# schemat.net
KiCad netlist of a schematic drawn in EAGLE
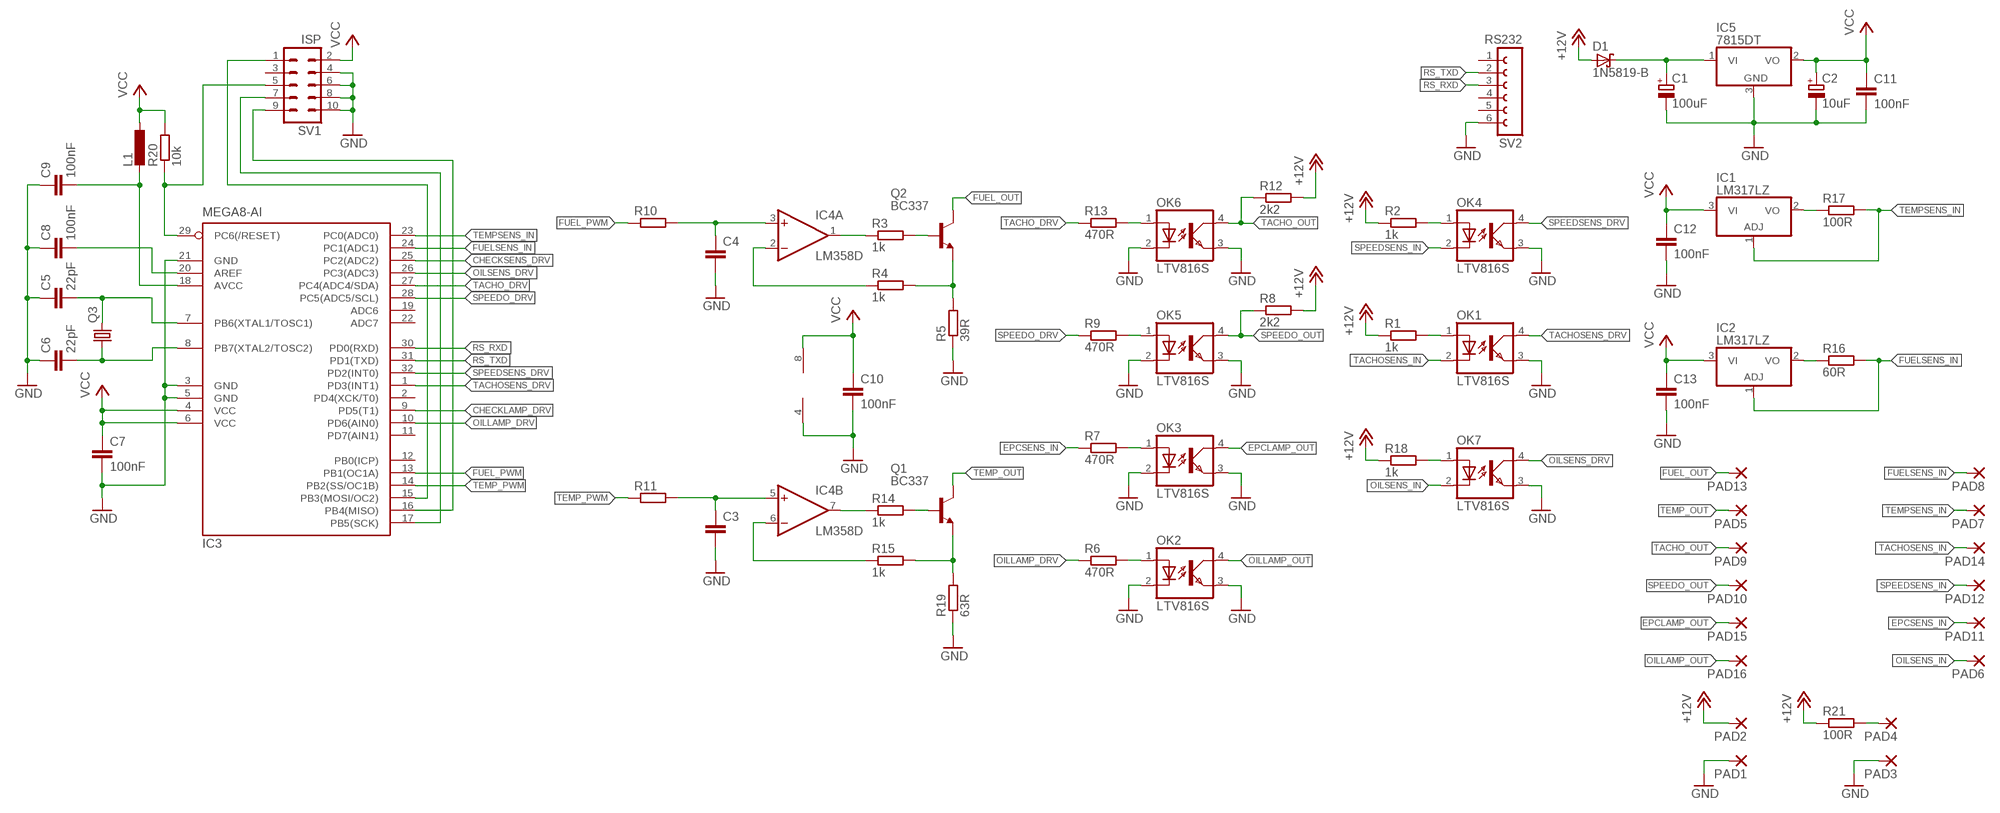
[diagram p0: schematic, sheet 1]

(export (version "E")
  (design (tool "Eeschema 10.0.6"))
  (components
    (comp (ref "C1")
      (value "100uF")
      (footprint "eagle-import:E2,5-6")
      (libsource (lib "eagle-import") (part "CPOL-EUE2.5-6"))
    )
    (comp (ref "C2")
      (value "10uF")
      (footprint "eagle-import:E2,5-6")
      (libsource (lib "eagle-import") (part "CPOL-EUE2.5-6"))
    )
    (comp (ref "C3")
      (value "C-EU025-025X050")
      (footprint "eagle-import:C025-025X050")
      (libsource (lib "eagle-import") (part "C-EU025-025X050"))
    )
    (comp (ref "C4")
      (value "C-EU025-025X050")
      (footprint "eagle-import:C025-025X050")
      (libsource (lib "eagle-import") (part "C-EU025-025X050"))
    )
    (comp (ref "C5")
      (value "22pF")
      (footprint "eagle-import:C0805")
      (libsource (lib "eagle-import") (part "C-EUC0805"))
    )
    (comp (ref "C6")
      (value "22pF")
      (footprint "eagle-import:C0805")
      (libsource (lib "eagle-import") (part "C-EUC0805"))
    )
    (comp (ref "C7")
      (value "100nF")
      (footprint "eagle-import:C0805")
      (libsource (lib "eagle-import") (part "C-EUC0805"))
    )
    (comp (ref "C8")
      (value "100nF")
      (footprint "eagle-import:C0805")
      (libsource (lib "eagle-import") (part "C-EUC0805"))
    )
    (comp (ref "C9")
      (value "100nF")
      (footprint "eagle-import:C0805")
      (libsource (lib "eagle-import") (part "C-EUC0805"))
    )
    (comp (ref "C10")
      (value "100nF")
      (footprint "eagle-import:C0805")
      (libsource (lib "eagle-import") (part "C-EUC0805"))
    )
    (comp (ref "C11")
      (value "100nF")
      (footprint "eagle-import:C0805")
      (libsource (lib "eagle-import") (part "C-EUC0805"))
    )
    (comp (ref "C12")
      (value "100nF")
      (footprint "eagle-import:C0805")
      (libsource (lib "eagle-import") (part "C-EUC0805"))
    )
    (comp (ref "C13")
      (value "100nF")
      (footprint "eagle-import:C0805")
      (libsource (lib "eagle-import") (part "C-EUC0805"))
    )
    (comp (ref "D1")
      (value "1N5819-B")
      (footprint "eagle-import:DO41-7.6")
      (libsource (lib "eagle-import") (part "1N5819-B"))
    )
    (comp (ref "IC1")
      (value "LM317LZ")
      (footprint "eagle-import:TO92")
      (libsource (lib "eagle-import") (part "317LZLM"))
    )
    (comp (ref "IC2")
      (value "LM317LZ")
      (footprint "eagle-import:TO92")
      (libsource (lib "eagle-import") (part "317LZLM"))
    )
    (comp (ref "IC3")
      (value "MEGA8-AI")
      (footprint "eagle-import:TQFP32-08")
      (fields (field (name "MPN") "ATMEGA8-16AU"))
      (libsource (lib "eagle-import") (part "MEGA8-AI"))
    )
    (comp (ref "IC4")
      (value "LM358D")
      (footprint "eagle-import:SO08")
      (libsource (lib "eagle-import") (part "LM358D"))
    )
    (comp (ref "IC5")
      (value "7815DT")
      (footprint "eagle-import:TO252")
      (libsource (lib "eagle-import") (part "78DT15"))
    )
    (comp (ref "L1")
      (value "L-EU0207/7")
      (footprint "eagle-import:0207_7")
      (libsource (lib "eagle-import") (part "L-EU0207/7"))
    )
    (comp (ref "OK1")
      (value "LTV816S")
      (footprint "eagle-import:SMD4")
      (libsource (lib "eagle-import") (part "LTV816S"))
    )
    (comp (ref "OK2")
      (value "LTV816S")
      (footprint "eagle-import:SMD4")
      (libsource (lib "eagle-import") (part "LTV816S"))
    )
    (comp (ref "OK3")
      (value "LTV816S")
      (footprint "eagle-import:SMD4")
      (libsource (lib "eagle-import") (part "LTV816S"))
    )
    (comp (ref "OK4")
      (value "LTV816S")
      (footprint "eagle-import:SMD4")
      (libsource (lib "eagle-import") (part "LTV816S"))
    )
    (comp (ref "OK5")
      (value "LTV816S")
      (footprint "eagle-import:SMD4")
      (libsource (lib "eagle-import") (part "LTV816S"))
    )
    (comp (ref "OK6")
      (value "LTV816S")
      (footprint "eagle-import:SMD4")
      (libsource (lib "eagle-import") (part "LTV816S"))
    )
    (comp (ref "OK7")
      (value "LTV816S")
      (footprint "eagle-import:SMD4")
      (libsource (lib "eagle-import") (part "LTV816S"))
    )
    (comp (ref "PAD1")
      (value "2,54/1,1")
      (footprint "eagle-import:2,54_1,1")
      (libsource (lib "eagle-import") (part "2,54/1,1"))
    )
    (comp (ref "PAD2")
      (value "2,54/1,1")
      (footprint "eagle-import:2,54_1,1")
      (libsource (lib "eagle-import") (part "2,54/1,1"))
    )
    (comp (ref "PAD3")
      (value "2,54/1,1")
      (footprint "eagle-import:2,54_1,1")
      (libsource (lib "eagle-import") (part "2,54/1,1"))
    )
    (comp (ref "PAD4")
      (value "2,54/1,1")
      (footprint "eagle-import:2,54_1,1")
      (libsource (lib "eagle-import") (part "2,54/1,1"))
    )
    (comp (ref "PAD5")
      (value "2,54/1,1")
      (footprint "eagle-import:2,54_1,1")
      (libsource (lib "eagle-import") (part "2,54/1,1"))
    )
    (comp (ref "PAD6")
      (value "2,54/1,1")
      (footprint "eagle-import:2,54_1,1")
      (libsource (lib "eagle-import") (part "2,54/1,1"))
    )
    (comp (ref "PAD7")
      (value "2,54/1,1")
      (footprint "eagle-import:2,54_1,1")
      (libsource (lib "eagle-import") (part "2,54/1,1"))
    )
    (comp (ref "PAD8")
      (value "2,54/1,1")
      (footprint "eagle-import:2,54_1,1")
      (libsource (lib "eagle-import") (part "2,54/1,1"))
    )
    (comp (ref "PAD9")
      (value "2,54/1,1")
      (footprint "eagle-import:2,54_1,1")
      (libsource (lib "eagle-import") (part "2,54/1,1"))
    )
    (comp (ref "PAD10")
      (value "2,54/1,1")
      (footprint "eagle-import:2,54_1,1")
      (libsource (lib "eagle-import") (part "2,54/1,1"))
    )
    (comp (ref "PAD11")
      (value "2,54/1,1")
      (footprint "eagle-import:2,54_1,1")
      (libsource (lib "eagle-import") (part "2,54/1,1"))
    )
    (comp (ref "PAD12")
      (value "2,54/1,1")
      (footprint "eagle-import:2,54_1,1")
      (libsource (lib "eagle-import") (part "2,54/1,1"))
    )
    (comp (ref "PAD13")
      (value "2,54/1,1")
      (footprint "eagle-import:2,54_1,1")
      (libsource (lib "eagle-import") (part "2,54/1,1"))
    )
    (comp (ref "PAD14")
      (value "2,54/1,1")
      (footprint "eagle-import:2,54_1,1")
      (libsource (lib "eagle-import") (part "2,54/1,1"))
    )
    (comp (ref "PAD15")
      (value "2,54/1,1")
      (footprint "eagle-import:2,54_1,1")
      (libsource (lib "eagle-import") (part "2,54/1,1"))
    )
    (comp (ref "PAD16")
      (value "2,54/1,1")
      (footprint "eagle-import:2,54_1,1")
      (libsource (lib "eagle-import") (part "2,54/1,1"))
    )
    (comp (ref "Q1")
      (value "BC337")
      (footprint "eagle-import:TO92")
      (libsource (lib "eagle-import") (part "BC337"))
    )
    (comp (ref "Q2")
      (value "BC337")
      (footprint "eagle-import:TO92")
      (libsource (lib "eagle-import") (part "BC337"))
    )
    (comp (ref "Q3")
      (value "CRYSTALHC49UP")
      (footprint "eagle-import:HC49UP")
      (libsource (lib "eagle-import") (part "CRYSTALHC49UP"))
    )
    (comp (ref "R1")
      (value "1k")
      (footprint "eagle-import:M0805")
      (libsource (lib "eagle-import") (part "R-EU_M0805"))
    )
    (comp (ref "R2")
      (value "1k")
      (footprint "eagle-import:M0805")
      (libsource (lib "eagle-import") (part "R-EU_M0805"))
    )
    (comp (ref "R3")
      (value "1k")
      (footprint "eagle-import:M0805")
      (libsource (lib "eagle-import") (part "R-EU_M0805"))
    )
    (comp (ref "R4")
      (value "1k")
      (footprint "eagle-import:M0805")
      (libsource (lib "eagle-import") (part "R-EU_M0805"))
    )
    (comp (ref "R5")
      (value "39R")
      (footprint "eagle-import:M0805")
      (libsource (lib "eagle-import") (part "R-EU_M0805"))
    )
    (comp (ref "R6")
      (value "470R")
      (footprint "eagle-import:M0805")
      (libsource (lib "eagle-import") (part "R-EU_M0805"))
    )
    (comp (ref "R7")
      (value "470R")
      (footprint "eagle-import:M0805")
      (libsource (lib "eagle-import") (part "R-EU_M0805"))
    )
    (comp (ref "R8")
      (value "2k2")
      (footprint "eagle-import:M0805")
      (libsource (lib "eagle-import") (part "R-EU_M0805"))
    )
    (comp (ref "R9")
      (value "470R")
      (footprint "eagle-import:M0805")
      (libsource (lib "eagle-import") (part "R-EU_M0805"))
    )
    (comp (ref "R10")
      (value "R-EU_M0805")
      (footprint "eagle-import:M0805")
      (libsource (lib "eagle-import") (part "R-EU_M0805"))
    )
    (comp (ref "R11")
      (value "R-EU_M0805")
      (footprint "eagle-import:M0805")
      (libsource (lib "eagle-import") (part "R-EU_M0805"))
    )
    (comp (ref "R12")
      (value "2k2")
      (footprint "eagle-import:M0805")
      (libsource (lib "eagle-import") (part "R-EU_M0805"))
    )
    (comp (ref "R13")
      (value "470R")
      (footprint "eagle-import:M0805")
      (libsource (lib "eagle-import") (part "R-EU_M0805"))
    )
    (comp (ref "R14")
      (value "1k")
      (footprint "eagle-import:M0805")
      (libsource (lib "eagle-import") (part "R-EU_M0805"))
    )
    (comp (ref "R15")
      (value "1k")
      (footprint "eagle-import:M0805")
      (libsource (lib "eagle-import") (part "R-EU_M0805"))
    )
    (comp (ref "R16")
      (value "60R")
      (footprint "eagle-import:M0805")
      (libsource (lib "eagle-import") (part "R-EU_M0805"))
    )
    (comp (ref "R17")
      (value "100R")
      (footprint "eagle-import:M0805")
      (libsource (lib "eagle-import") (part "R-EU_M0805"))
    )
    (comp (ref "R18")
      (value "1k")
      (footprint "eagle-import:M0805")
      (libsource (lib "eagle-import") (part "R-EU_M0805"))
    )
    (comp (ref "R19")
      (value "63R")
      (footprint "eagle-import:M0805")
      (libsource (lib "eagle-import") (part "R-EU_M0805"))
    )
    (comp (ref "R20")
      (value "10k")
      (footprint "eagle-import:M0805")
      (libsource (lib "eagle-import") (part "R-EU_M0805"))
    )
    (comp (ref "R21")
      (value "100R")
      (footprint "eagle-import:M0805")
      (libsource (lib "eagle-import") (part "R-EU_M0805"))
    )
    (comp (ref "SV1")
      (value "ISP")
      (footprint "eagle-import:ML10L")
      (libsource (lib "eagle-import") (part "ML10L"))
    )
    (comp (ref "SV2")
      (value "RS232")
      (footprint "eagle-import:FE06")
      (libsource (lib "eagle-import") (part "FE06-1"))
    )
  )
  (nets
    (net (code "1") (name "+12V") (class "Default")
      (node (ref "D1") (pin "A") (pinfunction "A_A") (pintype "passive"))
      (node (ref "PAD2") (pin "1") (pinfunction "P_1") (pintype "passive"))
      (node (ref "R1") (pin "1") (pinfunction "1_1") (pintype "passive"))
      (node (ref "R12") (pin "2") (pinfunction "2_2") (pintype "passive"))
      (node (ref "R18") (pin "1") (pinfunction "1_1") (pintype "passive"))
      (node (ref "R2") (pin "1") (pinfunction "1_1") (pintype "passive"))
      (node (ref "R21") (pin "1") (pinfunction "1_1") (pintype "passive"))
      (node (ref "R8") (pin "2") (pinfunction "2_2") (pintype "passive"))
    )
    (net (code "2") (name "CHECKLAMP_DRV") (class "Default")
      (node (ref "IC3") (pin "9") (pinfunction "PD5(T1)_9") (pintype "bidirectional"))
    )
    (net (code "3") (name "CHECKSENS_DRV") (class "Default")
      (node (ref "IC3") (pin "25") (pinfunction "PC2(ADC2)_25") (pintype "bidirectional"))
    )
    (net (code "4") (name "EPCLAMP_OUT") (class "Default")
      (node (ref "OK3") (pin "4") (pinfunction "COL_4") (pintype "passive"))
      (node (ref "PAD15") (pin "1") (pinfunction "P_1") (pintype "passive"))
    )
    (net (code "5") (name "EPCSENS_IN") (class "Default")
      (node (ref "PAD11") (pin "1") (pinfunction "P_1") (pintype "passive"))
      (node (ref "R7") (pin "1") (pinfunction "1_1") (pintype "passive"))
    )
    (net (code "6") (name "FUELSENS_IN") (class "Default")
      (node (ref "IC2") (pin "1") (pinfunction "ADJ_1") (pintype "input"))
      (node (ref "IC3") (pin "24") (pinfunction "PC1(ADC1)_24") (pintype "bidirectional"))
      (node (ref "PAD8") (pin "1") (pinfunction "P_1") (pintype "passive"))
      (node (ref "R16") (pin "2") (pinfunction "2_2") (pintype "passive"))
    )
    (net (code "7") (name "FUEL_OUT") (class "Default")
      (node (ref "PAD13") (pin "1") (pinfunction "P_1") (pintype "passive"))
      (node (ref "Q2") (pin "3") (pinfunction "C_3") (pintype "passive"))
    )
    (net (code "8") (name "FUEL_PWM") (class "Default")
      (node (ref "IC3") (pin "13") (pinfunction "PB1(OC1A)_13") (pintype "bidirectional"))
      (node (ref "R10") (pin "1") (pinfunction "1_1") (pintype "passive"))
    )
    (net (code "9") (name "GND") (class "Default")
      (node (ref "C1") (pin "-") (pinfunction "-_-") (pintype "passive"))
      (node (ref "C10") (pin "2") (pinfunction "2_2") (pintype "passive"))
      (node (ref "C11") (pin "2") (pinfunction "2_2") (pintype "passive"))
      (node (ref "C12") (pin "2") (pinfunction "2_2") (pintype "passive"))
      (node (ref "C13") (pin "2") (pinfunction "2_2") (pintype "passive"))
      (node (ref "C2") (pin "-") (pinfunction "-_-") (pintype "passive"))
      (node (ref "C3") (pin "2") (pinfunction "2_2") (pintype "passive"))
      (node (ref "C4") (pin "2") (pinfunction "2_2") (pintype "passive"))
      (node (ref "C5") (pin "1") (pinfunction "1_1") (pintype "passive"))
      (node (ref "C6") (pin "1") (pinfunction "1_1") (pintype "passive"))
      (node (ref "C7") (pin "2") (pinfunction "2_2") (pintype "passive"))
      (node (ref "C8") (pin "1") (pinfunction "1_1") (pintype "passive"))
      (node (ref "C9") (pin "1") (pinfunction "1_1") (pintype "passive"))
      (node (ref "IC3") (pin "21") (pinfunction "GND_21") (pintype "power_in"))
      (node (ref "IC3") (pin "3") (pinfunction "GND_3") (pintype "power_in"))
      (node (ref "IC3") (pin "5") (pinfunction "GND_5") (pintype "power_in"))
      (node (ref "IC4") (pin "4") (pinfunction "V-_4") (pintype "power_in"))
      (node (ref "IC5") (pin "3") (pinfunction "GND_3") (pintype "passive"))
      (node (ref "OK1") (pin "3") (pinfunction "EMIT_3") (pintype "passive"))
      (node (ref "OK2") (pin "2") (pinfunction "C_2") (pintype "passive"))
      (node (ref "OK2") (pin "3") (pinfunction "EMIT_3") (pintype "passive"))
      (node (ref "OK3") (pin "2") (pinfunction "C_2") (pintype "passive"))
      (node (ref "OK3") (pin "3") (pinfunction "EMIT_3") (pintype "passive"))
      (node (ref "OK4") (pin "3") (pinfunction "EMIT_3") (pintype "passive"))
      (node (ref "OK5") (pin "2") (pinfunction "C_2") (pintype "passive"))
      (node (ref "OK5") (pin "3") (pinfunction "EMIT_3") (pintype "passive"))
      (node (ref "OK6") (pin "2") (pinfunction "C_2") (pintype "passive"))
      (node (ref "OK6") (pin "3") (pinfunction "EMIT_3") (pintype "passive"))
      (node (ref "OK7") (pin "3") (pinfunction "EMIT_3") (pintype "passive"))
      (node (ref "PAD1") (pin "1") (pinfunction "P_1") (pintype "passive"))
      (node (ref "PAD3") (pin "1") (pinfunction "P_1") (pintype "passive"))
      (node (ref "R19") (pin "1") (pinfunction "1_1") (pintype "passive"))
      (node (ref "R5") (pin "1") (pinfunction "1_1") (pintype "passive"))
      (node (ref "SV1") (pin "10") (pinfunction "10_10") (pintype "passive"))
      (node (ref "SV1") (pin "4") (pinfunction "4_4") (pintype "passive"))
      (node (ref "SV1") (pin "6") (pinfunction "6_6") (pintype "passive"))
      (node (ref "SV1") (pin "8") (pinfunction "8_8") (pintype "passive"))
      (node (ref "SV2") (pin "6") (pinfunction "6_6") (pintype "passive"))
    )
    (net (code "10") (name "Net-(IC1-VO)") (class "Default")
      (node (ref "IC1") (pin "2") (pinfunction "VO_2") (pintype "passive"))
      (node (ref "R17") (pin "1") (pinfunction "1_1") (pintype "passive"))
    )
    (net (code "11") (name "Net-(IC2-VO)") (class "Default")
      (node (ref "IC2") (pin "2") (pinfunction "VO_2") (pintype "passive"))
      (node (ref "R16") (pin "1") (pinfunction "1_1") (pintype "passive"))
    )
    (net (code "12") (name "Net-(IC3-AREF)") (class "Default")
      (node (ref "C8") (pin "2") (pinfunction "2_2") (pintype "passive"))
      (node (ref "IC3") (pin "20") (pinfunction "AREF_20") (pintype "passive"))
    )
    (net (code "13") (name "Net-(IC3-AVCC)") (class "Default")
      (node (ref "C9") (pin "2") (pinfunction "2_2") (pintype "passive"))
      (node (ref "IC3") (pin "18") (pinfunction "AVCC_18") (pintype "power_in"))
      (node (ref "L1") (pin "2") (pinfunction "2_2") (pintype "passive"))
    )
    (net (code "14") (name "Net-(IC3-PB3(MOSI{slash}OC2))") (class "Default")
      (node (ref "IC3") (pin "15") (pinfunction "PB3(MOSI/OC2)_15") (pintype "bidirectional"))
      (node (ref "SV1") (pin "1") (pinfunction "1_1") (pintype "passive"))
    )
    (net (code "15") (name "Net-(IC3-PB4(MISO))") (class "Default")
      (node (ref "IC3") (pin "16") (pinfunction "PB4(MISO)_16") (pintype "bidirectional"))
      (node (ref "SV1") (pin "9") (pinfunction "9_9") (pintype "passive"))
    )
    (net (code "16") (name "Net-(IC3-PB5(SCK))") (class "Default")
      (node (ref "IC3") (pin "17") (pinfunction "PB5(SCK)_17") (pintype "bidirectional"))
      (node (ref "SV1") (pin "7") (pinfunction "7_7") (pintype "passive"))
    )
    (net (code "17") (name "Net-(IC3-PB6(XTAL1{slash}TOSC1))") (class "Default")
      (node (ref "C5") (pin "2") (pinfunction "2_2") (pintype "passive"))
      (node (ref "IC3") (pin "7") (pinfunction "PB6(XTAL1/TOSC1)_7") (pintype "bidirectional"))
      (node (ref "Q3") (pin "2") (pinfunction "2_2") (pintype "passive"))
    )
    (net (code "18") (name "Net-(IC3-PB7(XTAL2{slash}TOSC2))") (class "Default")
      (node (ref "C6") (pin "2") (pinfunction "2_2") (pintype "passive"))
      (node (ref "IC3") (pin "8") (pinfunction "PB7(XTAL2/TOSC2)_8") (pintype "bidirectional"))
      (node (ref "Q3") (pin "1") (pinfunction "1_1") (pintype "passive"))
    )
    (net (code "19") (name "Net-(IC3-PC6({slash}RESET))") (class "Default")
      (node (ref "IC3") (pin "29") (pinfunction "PC6(/RESET)_29") (pintype "bidirectional"))
      (node (ref "R20") (pin "1") (pinfunction "1_1") (pintype "passive"))
      (node (ref "SV1") (pin "5") (pinfunction "5_5") (pintype "passive"))
    )
    (net (code "20") (name "Net-(IC4A-+IN)") (class "Default")
      (node (ref "C4") (pin "1") (pinfunction "1_1") (pintype "passive"))
      (node (ref "IC4") (pin "3") (pinfunction "+IN_3") (pintype "input"))
      (node (ref "R10") (pin "2") (pinfunction "2_2") (pintype "passive"))
    )
    (net (code "21") (name "Net-(IC4A--IN)") (class "Default")
      (node (ref "IC4") (pin "2") (pinfunction "-IN_2") (pintype "input"))
      (node (ref "R4") (pin "1") (pinfunction "1_1") (pintype "passive"))
    )
    (net (code "22") (name "Net-(IC4A-OUT)") (class "Default")
      (node (ref "IC4") (pin "1") (pinfunction "OUT_1") (pintype "output"))
      (node (ref "R3") (pin "1") (pinfunction "1_1") (pintype "passive"))
    )
    (net (code "23") (name "Net-(IC4B-+IN)") (class "Default")
      (node (ref "C3") (pin "1") (pinfunction "1_1") (pintype "passive"))
      (node (ref "IC4") (pin "5") (pinfunction "+IN_5") (pintype "input"))
      (node (ref "R11") (pin "2") (pinfunction "2_2") (pintype "passive"))
    )
    (net (code "24") (name "Net-(IC4B--IN)") (class "Default")
      (node (ref "IC4") (pin "6") (pinfunction "-IN_6") (pintype "input"))
      (node (ref "R15") (pin "1") (pinfunction "1_1") (pintype "passive"))
    )
    (net (code "25") (name "Net-(IC4B-OUT)") (class "Default")
      (node (ref "IC4") (pin "7") (pinfunction "OUT_7") (pintype "output"))
      (node (ref "R14") (pin "1") (pinfunction "1_1") (pintype "passive"))
    )
    (net (code "26") (name "Net-(IC5-VI)") (class "Default")
      (node (ref "C1") (pin "+") (pinfunction "+_+") (pintype "passive"))
      (node (ref "D1") (pin "C") (pinfunction "C_C") (pintype "passive"))
      (node (ref "IC5") (pin "1") (pinfunction "VI_1") (pintype "input"))
    )
    (net (code "27") (name "Net-(OK1-A)") (class "Default")
      (node (ref "OK1") (pin "1") (pinfunction "A_1") (pintype "passive"))
      (node (ref "R1") (pin "2") (pinfunction "2_2") (pintype "passive"))
    )
    (net (code "28") (name "Net-(OK2-A)") (class "Default")
      (node (ref "OK2") (pin "1") (pinfunction "A_1") (pintype "passive"))
      (node (ref "R6") (pin "2") (pinfunction "2_2") (pintype "passive"))
    )
    (net (code "29") (name "Net-(OK3-A)") (class "Default")
      (node (ref "OK3") (pin "1") (pinfunction "A_1") (pintype "passive"))
      (node (ref "R7") (pin "2") (pinfunction "2_2") (pintype "passive"))
    )
    (net (code "30") (name "Net-(OK4-A)") (class "Default")
      (node (ref "OK4") (pin "1") (pinfunction "A_1") (pintype "passive"))
      (node (ref "R2") (pin "2") (pinfunction "2_2") (pintype "passive"))
    )
    (net (code "31") (name "Net-(OK5-A)") (class "Default")
      (node (ref "OK5") (pin "1") (pinfunction "A_1") (pintype "passive"))
      (node (ref "R9") (pin "2") (pinfunction "2_2") (pintype "passive"))
    )
    (net (code "32") (name "Net-(OK6-A)") (class "Default")
      (node (ref "OK6") (pin "1") (pinfunction "A_1") (pintype "passive"))
      (node (ref "R13") (pin "2") (pinfunction "2_2") (pintype "passive"))
    )
    (net (code "33") (name "Net-(OK7-A)") (class "Default")
      (node (ref "OK7") (pin "1") (pinfunction "A_1") (pintype "passive"))
      (node (ref "R18") (pin "2") (pinfunction "2_2") (pintype "passive"))
    )
    (net (code "34") (name "Net-(PAD4-P)") (class "Default")
      (node (ref "PAD4") (pin "1") (pinfunction "P_1") (pintype "passive"))
      (node (ref "R21") (pin "2") (pinfunction "2_2") (pintype "passive"))
    )
    (net (code "35") (name "Net-(Q1-B)") (class "Default")
      (node (ref "Q1") (pin "2") (pinfunction "B_2") (pintype "passive"))
      (node (ref "R14") (pin "2") (pinfunction "2_2") (pintype "passive"))
    )
    (net (code "36") (name "Net-(Q1-E)") (class "Default")
      (node (ref "Q1") (pin "1") (pinfunction "E_1") (pintype "passive"))
      (node (ref "R15") (pin "2") (pinfunction "2_2") (pintype "passive"))
      (node (ref "R19") (pin "2") (pinfunction "2_2") (pintype "passive"))
    )
    (net (code "37") (name "Net-(Q2-B)") (class "Default")
      (node (ref "Q2") (pin "2") (pinfunction "B_2") (pintype "passive"))
      (node (ref "R3") (pin "2") (pinfunction "2_2") (pintype "passive"))
    )
    (net (code "38") (name "Net-(Q2-E)") (class "Default")
      (node (ref "Q2") (pin "1") (pinfunction "E_1") (pintype "passive"))
      (node (ref "R4") (pin "2") (pinfunction "2_2") (pintype "passive"))
      (node (ref "R5") (pin "2") (pinfunction "2_2") (pintype "passive"))
    )
    (net (code "39") (name "OILLAMP_DRV") (class "Default")
      (node (ref "IC3") (pin "10") (pinfunction "PD6(AIN0)_10") (pintype "bidirectional"))
      (node (ref "R6") (pin "1") (pinfunction "1_1") (pintype "passive"))
    )
    (net (code "40") (name "OILLAMP_OUT") (class "Default")
      (node (ref "OK2") (pin "4") (pinfunction "COL_4") (pintype "passive"))
      (node (ref "PAD16") (pin "1") (pinfunction "P_1") (pintype "passive"))
    )
    (net (code "41") (name "OILSENS_DRV") (class "Default")
      (node (ref "IC3") (pin "26") (pinfunction "PC3(ADC3)_26") (pintype "bidirectional"))
      (node (ref "OK7") (pin "4") (pinfunction "COL_4") (pintype "passive"))
    )
    (net (code "42") (name "OILSENS_IN") (class "Default")
      (node (ref "OK7") (pin "2") (pinfunction "C_2") (pintype "passive"))
      (node (ref "PAD6") (pin "1") (pinfunction "P_1") (pintype "passive"))
    )
    (net (code "43") (name "RS_RXD") (class "Default")
      (node (ref "IC3") (pin "30") (pinfunction "PD0(RXD)_30") (pintype "bidirectional"))
      (node (ref "SV2") (pin "3") (pinfunction "3_3") (pintype "passive"))
    )
    (net (code "44") (name "RS_TXD") (class "Default")
      (node (ref "IC3") (pin "31") (pinfunction "PD1(TXD)_31") (pintype "bidirectional"))
      (node (ref "SV2") (pin "2") (pinfunction "2_2") (pintype "passive"))
    )
    (net (code "45") (name "SPEEDO_DRV") (class "Default")
      (node (ref "IC3") (pin "28") (pinfunction "PC5(ADC5/SCL)_28") (pintype "bidirectional"))
      (node (ref "R9") (pin "1") (pinfunction "1_1") (pintype "passive"))
    )
    (net (code "46") (name "SPEEDO_OUT") (class "Default")
      (node (ref "OK5") (pin "4") (pinfunction "COL_4") (pintype "passive"))
      (node (ref "PAD10") (pin "1") (pinfunction "P_1") (pintype "passive"))
      (node (ref "R8") (pin "1") (pinfunction "1_1") (pintype "passive"))
    )
    (net (code "47") (name "SPEEDSENS_DRV") (class "Default")
      (node (ref "IC3") (pin "32") (pinfunction "PD2(INT0)_32") (pintype "bidirectional"))
      (node (ref "OK4") (pin "4") (pinfunction "COL_4") (pintype "passive"))
    )
    (net (code "48") (name "SPEEDSENS_IN") (class "Default")
      (node (ref "OK4") (pin "2") (pinfunction "C_2") (pintype "passive"))
      (node (ref "PAD12") (pin "1") (pinfunction "P_1") (pintype "passive"))
    )
    (net (code "49") (name "TACHOSENS_DRV") (class "Default")
      (node (ref "IC3") (pin "1") (pinfunction "PD3(INT1)_1") (pintype "bidirectional"))
      (node (ref "OK1") (pin "4") (pinfunction "COL_4") (pintype "passive"))
    )
    (net (code "50") (name "TACHOSENS_IN") (class "Default")
      (node (ref "OK1") (pin "2") (pinfunction "C_2") (pintype "passive"))
      (node (ref "PAD14") (pin "1") (pinfunction "P_1") (pintype "passive"))
    )
    (net (code "51") (name "TACHO_DRV") (class "Default")
      (node (ref "IC3") (pin "27") (pinfunction "PC4(ADC4/SDA)_27") (pintype "bidirectional"))
      (node (ref "R13") (pin "1") (pinfunction "1_1") (pintype "passive"))
    )
    (net (code "52") (name "TACHO_OUT") (class "Default")
      (node (ref "OK6") (pin "4") (pinfunction "COL_4") (pintype "passive"))
      (node (ref "PAD9") (pin "1") (pinfunction "P_1") (pintype "passive"))
      (node (ref "R12") (pin "1") (pinfunction "1_1") (pintype "passive"))
    )
    (net (code "53") (name "TEMPSENS_IN") (class "Default")
      (node (ref "IC1") (pin "1") (pinfunction "ADJ_1") (pintype "input"))
      (node (ref "IC3") (pin "23") (pinfunction "PC0(ADC0)_23") (pintype "bidirectional"))
      (node (ref "PAD7") (pin "1") (pinfunction "P_1") (pintype "passive"))
      (node (ref "R17") (pin "2") (pinfunction "2_2") (pintype "passive"))
    )
    (net (code "54") (name "TEMP_OUT") (class "Default")
      (node (ref "PAD5") (pin "1") (pinfunction "P_1") (pintype "passive"))
      (node (ref "Q1") (pin "3") (pinfunction "C_3") (pintype "passive"))
    )
    (net (code "55") (name "TEMP_PWM") (class "Default")
      (node (ref "IC3") (pin "14") (pinfunction "PB2(SS/OC1B)_14") (pintype "bidirectional"))
      (node (ref "R11") (pin "1") (pinfunction "1_1") (pintype "passive"))
    )
    (net (code "56") (name "VCC") (class "Default")
      (node (ref "C10") (pin "1") (pinfunction "1_1") (pintype "passive"))
      (node (ref "C11") (pin "1") (pinfunction "1_1") (pintype "passive"))
      (node (ref "C12") (pin "1") (pinfunction "1_1") (pintype "passive"))
      (node (ref "C13") (pin "1") (pinfunction "1_1") (pintype "passive"))
      (node (ref "C2") (pin "+") (pinfunction "+_+") (pintype "passive"))
      (node (ref "C7") (pin "1") (pinfunction "1_1") (pintype "passive"))
      (node (ref "IC1") (pin "3") (pinfunction "VI_3") (pintype "input"))
      (node (ref "IC2") (pin "3") (pinfunction "VI_3") (pintype "input"))
      (node (ref "IC3") (pin "4") (pinfunction "VCC_4") (pintype "power_in"))
      (node (ref "IC3") (pin "6") (pinfunction "VCC_6") (pintype "power_in"))
      (node (ref "IC4") (pin "8") (pinfunction "V+_8") (pintype "power_in"))
      (node (ref "IC5") (pin "2") (pinfunction "VO_2") (pintype "passive"))
      (node (ref "L1") (pin "1") (pinfunction "1_1") (pintype "passive"))
      (node (ref "R20") (pin "2") (pinfunction "2_2") (pintype "passive"))
      (node (ref "SV1") (pin "2") (pinfunction "2_2") (pintype "passive"))
    )
    (net (code "57") (name "unconnected-(IC3-ADC6-Pad19)") (class "Default")
      (node (ref "IC3") (pin "19") (pinfunction "ADC6_19") (pintype "bidirectional"))
    )
    (net (code "58") (name "unconnected-(IC3-ADC7-Pad22)") (class "Default")
      (node (ref "IC3") (pin "22") (pinfunction "ADC7_22") (pintype "bidirectional"))
    )
    (net (code "59") (name "unconnected-(IC3-PB0(ICP)-Pad12)") (class "Default")
      (node (ref "IC3") (pin "12") (pinfunction "PB0(ICP)_12") (pintype "bidirectional"))
    )
    (net (code "60") (name "unconnected-(IC3-PD4(XCK{slash}T0)-Pad2)") (class "Default")
      (node (ref "IC3") (pin "2") (pinfunction "PD4(XCK/T0)_2") (pintype "bidirectional"))
    )
    (net (code "61") (name "unconnected-(IC3-PD7(AIN1)-Pad11)") (class "Default")
      (node (ref "IC3") (pin "11") (pinfunction "PD7(AIN1)_11") (pintype "bidirectional"))
    )
    (net (code "62") (name "unconnected-(SV1-Pad3)") (class "Default")
      (node (ref "SV1") (pin "3") (pinfunction "3_3") (pintype "passive"))
    )
    (net (code "63") (name "unconnected-(SV2-Pad1)") (class "Default")
      (node (ref "SV2") (pin "1") (pinfunction "1_1") (pintype "passive"))
    )
    (net (code "64") (name "unconnected-(SV2-Pad4)") (class "Default")
      (node (ref "SV2") (pin "4") (pinfunction "4_4") (pintype "passive"))
    )
    (net (code "65") (name "unconnected-(SV2-Pad5)") (class "Default")
      (node (ref "SV2") (pin "5") (pinfunction "5_5") (pintype "passive"))
    )
  )
)
